# bpod_stepper_1_4_1.net
KiCad netlist of a schematic drawn in EAGLE
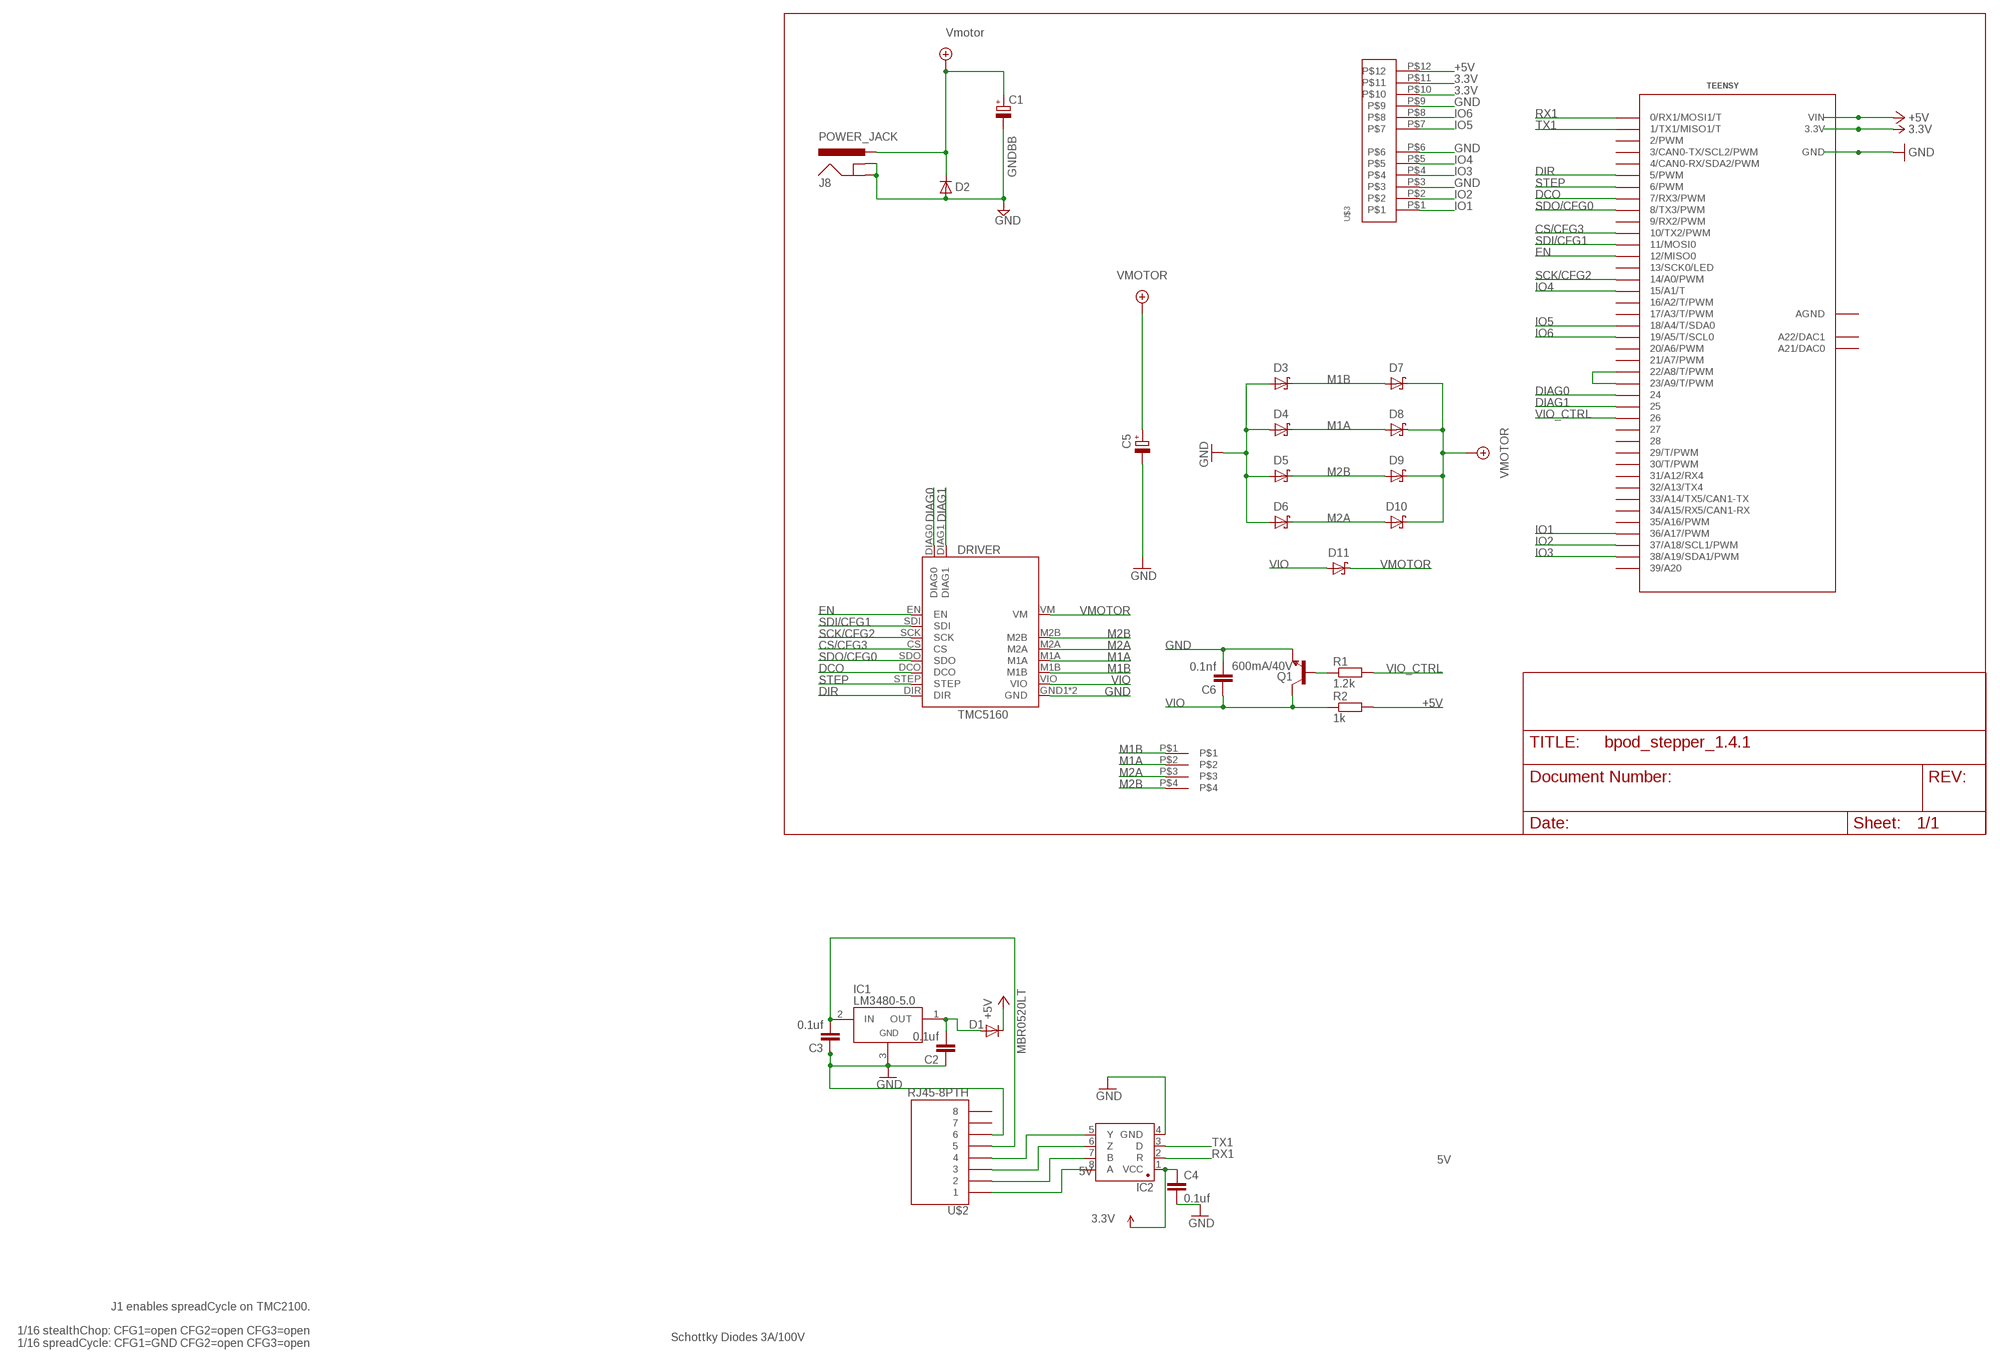
[diagram p0: schematic, sheet 1]

(export (version "E")
  (design (tool "Eeschema 10.0.6"))
  (components
    (comp (ref "C1")
      (value "CPOL-EUG")
      (footprint "eagle-import:PANASONIC_G")
      (libsource (lib "eagle-import") (part "CPOL-EUG"))
    )
    (comp (ref "C2")
      (value "0.1uf")
      (footprint "eagle-import:1206@1")
      (libsource (lib "eagle-import") (part "CAP1206"))
    )
    (comp (ref "C3")
      (value "0.1uf")
      (footprint "eagle-import:1206@1")
      (libsource (lib "eagle-import") (part "CAP1206"))
    )
    (comp (ref "C4")
      (value "0.1uf")
      (footprint "eagle-import:1206@1")
      (libsource (lib "eagle-import") (part "CAP1206"))
    )
    (comp (ref "C5")
      (value "CPOL-EUG")
      (footprint "eagle-import:PANASONIC_G")
      (libsource (lib "eagle-import") (part "CPOL-EUG"))
    )
    (comp (ref "C6")
      (value "0.1nf")
      (footprint "eagle-import:1206@1")
      (libsource (lib "eagle-import") (part "CAP1206"))
    )
    (comp (ref "D1")
      (value "MBR0520LT")
      (footprint "eagle-import:SOD123")
      (libsource (lib "eagle-import") (part "MBR0520LT"))
    )
    (comp (ref "D2")
      (value "DIODE-DO214AA")
      (footprint "eagle-import:DO214AA")
      (libsource (lib "eagle-import") (part "DIODE-DO214AA"))
    )
    (comp (ref "D3")
      (value "S310FA")
      (footprint "eagle-import:SOD123")
      (libsource (lib "eagle-import") (part "D_SCHOTTKY-SOD123"))
    )
    (comp (ref "D4")
      (value "S310FA")
      (footprint "eagle-import:SOD123")
      (libsource (lib "eagle-import") (part "D_SCHOTTKY-SOD123"))
    )
    (comp (ref "D5")
      (value "S310FA")
      (footprint "eagle-import:SOD123")
      (libsource (lib "eagle-import") (part "D_SCHOTTKY-SOD123"))
    )
    (comp (ref "D6")
      (value "S310FA")
      (footprint "eagle-import:SOD123")
      (libsource (lib "eagle-import") (part "D_SCHOTTKY-SOD123"))
    )
    (comp (ref "D7")
      (value "S310FA")
      (footprint "eagle-import:SOD123")
      (libsource (lib "eagle-import") (part "D_SCHOTTKY-SOD123"))
    )
    (comp (ref "D8")
      (value "S310FA")
      (footprint "eagle-import:SOD123")
      (libsource (lib "eagle-import") (part "D_SCHOTTKY-SOD123"))
    )
    (comp (ref "D9")
      (value "S310FA")
      (footprint "eagle-import:SOD123")
      (libsource (lib "eagle-import") (part "D_SCHOTTKY-SOD123"))
    )
    (comp (ref "D10")
      (value "S310FA")
      (footprint "eagle-import:SOD123")
      (libsource (lib "eagle-import") (part "D_SCHOTTKY-SOD123"))
    )
    (comp (ref "D11")
      (value "S310FA")
      (footprint "eagle-import:SOD123")
      (libsource (lib "eagle-import") (part "D_SCHOTTKY-SOD123"))
    )
    (comp (ref "DRIVER")
      (value "TMC5160")
      (footprint "eagle-import:TMC5160")
      (libsource (lib "eagle-import") (part "TMC5160"))
    )
    (comp (ref "IC1")
      (value "LM3480-5.0")
      (footprint "eagle-import:SOT-23-3")
      (libsource (lib "eagle-import") (part "LM3480-5.0"))
    )
    (comp (ref "IC2")
      (value "SN65HVD31DR")
      (footprint "eagle-import:SO08")
      (libsource (lib "eagle-import") (part "SN65HVD31DR"))
    )
    (comp (ref "J8")
      (value "POWER_JACK")
      (footprint "eagle-import:POWER_JACK_PTH")
      (libsource (lib "eagle-import") (part "POWER_JACK"))
    )
    (comp (ref "Q1")
      (value "600mA/40V")
      (footprint "eagle-import:SOT23-3")
      (libsource (lib "eagle-import") (part "TRANS_NPN-MMBT2222AL"))
    )
    (comp (ref "R1")
      (value "1.2k")
      (footprint "eagle-import:R1206")
      (libsource (lib "eagle-import") (part "R-EU_R1206"))
    )
    (comp (ref "R2")
      (value "1k")
      (footprint "eagle-import:R1206")
      (libsource (lib "eagle-import") (part "R-EU_R1206"))
    )
    (comp (ref "TEENSY")
      (value "TEENSY_3.6_DIL")
      (footprint "eagle-import:TEENSY_3.6_DIL")
      (libsource (lib "eagle-import") (part "TEENSY_3.6_DIL"))
    )
    (comp (ref "U$2")
      (value "RJ45-8PTH")
      (footprint "eagle-import:RJ45-8")
      (libsource (lib "eagle-import") (part "RJ45-8PTH"))
    )
    (comp (ref "U$3")
      (value "12POS_MOLEX_SOCKET")
      (footprint "eagle-import:12POS_MOLEX_SOCKET")
      (libsource (lib "eagle-import") (part "12POS_MOLEX_SOCKET"))
    )
    (comp (ref "U$4")
      (value "MOLEX395221004")
      (footprint "eagle-import:MOLEX395221004")
      (libsource (lib "eagle-import") (part "MOLEX395221004"))
    )
  )
  (nets
    (net (code "1") (name "+5V") (class "Default")
      (node (ref "D1") (pin "C") (pinfunction "C_C") (pintype "passive"))
      (node (ref "R2") (pin "2") (pinfunction "2_2") (pintype "passive"))
      (node (ref "TEENSY") (pin "VIN") (pinfunction "VIN_VIN") (pintype "power_in"))
      (node (ref "U$3") (pin "P$12") (pinfunction "P$12_P$12") (pintype "bidirectional"))
    )
    (net (code "2") (name "/AGND") (class "Default")
      (node (ref "TEENSY") (pin "AGND") (pinfunction "AGND_AGND") (pintype "power_in"))
    )
    (net (code "3") (name "/CS{slash}CFG3") (class "Default")
      (node (ref "DRIVER") (pin "CS") (pinfunction "CS_CS") (pintype "passive"))
      (node (ref "TEENSY") (pin "10") (pinfunction "10/TX2/PWM_10") (pintype "bidirectional"))
    )
    (net (code "4") (name "/DCO") (class "Default")
      (node (ref "DRIVER") (pin "DCO") (pinfunction "DCO_DCO") (pintype "passive"))
      (node (ref "TEENSY") (pin "7") (pinfunction "7/RX3/PWM_7") (pintype "bidirectional"))
    )
    (net (code "5") (name "/DIAG0") (class "Default")
      (node (ref "DRIVER") (pin "DIAG0") (pinfunction "DIAG0_DIAG0") (pintype "passive"))
      (node (ref "TEENSY") (pin "24") (pinfunction "24_24") (pintype "bidirectional"))
    )
    (net (code "6") (name "/DIAG1") (class "Default")
      (node (ref "DRIVER") (pin "DIAG1") (pinfunction "DIAG1_DIAG1") (pintype "passive"))
      (node (ref "TEENSY") (pin "25") (pinfunction "25_25") (pintype "bidirectional"))
    )
    (net (code "7") (name "/DIR") (class "Default")
      (node (ref "DRIVER") (pin "DIR") (pinfunction "DIR_DIR") (pintype "input"))
      (node (ref "TEENSY") (pin "5") (pinfunction "5/PWM_5") (pintype "bidirectional"))
    )
    (net (code "8") (name "/EN") (class "Default")
      (node (ref "DRIVER") (pin "EN") (pinfunction "EN_EN") (pintype "passive"))
      (node (ref "TEENSY") (pin "12") (pinfunction "12/MISO0_12") (pintype "bidirectional"))
    )
    (net (code "9") (name "/IO1") (class "Default")
      (node (ref "TEENSY") (pin "36/A17") (pinfunction "36/A17/PWM_36/A17") (pintype "bidirectional"))
      (node (ref "U$3") (pin "P$1") (pinfunction "P$1_P$1") (pintype "bidirectional"))
    )
    (net (code "10") (name "/IO2") (class "Default")
      (node (ref "TEENSY") (pin "37/A18") (pinfunction "37/A18/SCL1/PWM_37/A18") (pintype "bidirectional"))
      (node (ref "U$3") (pin "P$2") (pinfunction "P$2_P$2") (pintype "bidirectional"))
    )
    (net (code "11") (name "/IO3") (class "Default")
      (node (ref "TEENSY") (pin "38/A19") (pinfunction "38/A19/SDA1/PWM_38/A19") (pintype "bidirectional"))
      (node (ref "U$3") (pin "P$4") (pinfunction "P$4_P$4") (pintype "bidirectional"))
    )
    (net (code "12") (name "/IO4") (class "Default")
      (node (ref "TEENSY") (pin "15/A1") (pinfunction "15/A1/T_15/A1") (pintype "bidirectional"))
      (node (ref "U$3") (pin "P$5") (pinfunction "P$5_P$5") (pintype "bidirectional"))
    )
    (net (code "13") (name "/IO5") (class "Default")
      (node (ref "TEENSY") (pin "18/A4") (pinfunction "18/A4/T/SDA0_18/A4") (pintype "bidirectional"))
      (node (ref "U$3") (pin "P$7") (pinfunction "P$7_P$7") (pintype "bidirectional"))
    )
    (net (code "14") (name "/IO6") (class "Default")
      (node (ref "TEENSY") (pin "19/A5") (pinfunction "19/A5/T/SCL0_19/A5") (pintype "bidirectional"))
      (node (ref "U$3") (pin "P$8") (pinfunction "P$8_P$8") (pintype "bidirectional"))
    )
    (net (code "15") (name "/M1A") (class "Default")
      (node (ref "D4") (pin "C") (pinfunction "C_C") (pintype "passive"))
      (node (ref "D8") (pin "A") (pinfunction "A_A") (pintype "passive"))
      (node (ref "DRIVER") (pin "M1A") (pinfunction "M1A_M1A") (pintype "output"))
      (node (ref "U$4") (pin "P$2") (pinfunction "P$2_P$2") (pintype "bidirectional"))
    )
    (net (code "16") (name "/M1B") (class "Default")
      (node (ref "D3") (pin "C") (pinfunction "C_C") (pintype "passive"))
      (node (ref "D7") (pin "A") (pinfunction "A_A") (pintype "passive"))
      (node (ref "DRIVER") (pin "M1B") (pinfunction "M1B_M1B") (pintype "output"))
      (node (ref "U$4") (pin "P$1") (pinfunction "P$1_P$1") (pintype "bidirectional"))
    )
    (net (code "17") (name "/M2A") (class "Default")
      (node (ref "D10") (pin "A") (pinfunction "A_A") (pintype "passive"))
      (node (ref "D6") (pin "C") (pinfunction "C_C") (pintype "passive"))
      (node (ref "DRIVER") (pin "M2A") (pinfunction "M2A_M2A") (pintype "output"))
      (node (ref "U$4") (pin "P$3") (pinfunction "P$3_P$3") (pintype "bidirectional"))
    )
    (net (code "18") (name "/M2B") (class "Default")
      (node (ref "D5") (pin "C") (pinfunction "C_C") (pintype "passive"))
      (node (ref "D9") (pin "A") (pinfunction "A_A") (pintype "passive"))
      (node (ref "DRIVER") (pin "M2B") (pinfunction "M2B_M2B") (pintype "output"))
      (node (ref "U$4") (pin "P$4") (pinfunction "P$4_P$4") (pintype "bidirectional"))
    )
    (net (code "19") (name "/RX1") (class "Default")
      (node (ref "IC2") (pin "2") (pinfunction "R_2") (pintype "bidirectional"))
      (node (ref "TEENSY") (pin "0") (pinfunction "0/RX1/MOSI1/T_0") (pintype "bidirectional"))
    )
    (net (code "20") (name "/SCK{slash}CFG2") (class "Default")
      (node (ref "DRIVER") (pin "SCK") (pinfunction "SCK_SCK") (pintype "passive"))
      (node (ref "TEENSY") (pin "14/A0") (pinfunction "14/A0/PWM_14/A0") (pintype "bidirectional"))
    )
    (net (code "21") (name "/SDI{slash}CFG1") (class "Default")
      (node (ref "DRIVER") (pin "SDI") (pinfunction "SDI_SDI") (pintype "passive"))
      (node (ref "TEENSY") (pin "11") (pinfunction "11/MOSI0_11") (pintype "bidirectional"))
    )
    (net (code "22") (name "/SDO{slash}CFG0") (class "Default")
      (node (ref "DRIVER") (pin "SDO") (pinfunction "SDO_SDO") (pintype "passive"))
      (node (ref "TEENSY") (pin "8") (pinfunction "8/TX3/PWM_8") (pintype "bidirectional"))
    )
    (net (code "23") (name "/STEP") (class "Default")
      (node (ref "DRIVER") (pin "STEP") (pinfunction "STEP_STEP") (pintype "input"))
      (node (ref "TEENSY") (pin "6") (pinfunction "6/PWM_6") (pintype "bidirectional"))
    )
    (net (code "24") (name "/TX1") (class "Default")
      (node (ref "IC2") (pin "3") (pinfunction "D_3") (pintype "bidirectional"))
      (node (ref "TEENSY") (pin "1") (pinfunction "1/TX1/MISO1/T_1") (pintype "bidirectional"))
    )
    (net (code "25") (name "/VIO") (class "Default")
      (node (ref "C6") (pin "1") (pinfunction "1_1") (pintype "passive"))
      (node (ref "D11") (pin "A") (pinfunction "A_A") (pintype "passive"))
      (node (ref "DRIVER") (pin "VIO") (pinfunction "VIO_VIO") (pintype "power_in"))
      (node (ref "Q1") (pin "3") (pinfunction "C_3") (pintype "passive"))
      (node (ref "R2") (pin "1") (pinfunction "1_1") (pintype "passive"))
    )
    (net (code "26") (name "/VIO_CTRL") (class "Default")
      (node (ref "R1") (pin "2") (pinfunction "2_2") (pintype "passive"))
      (node (ref "TEENSY") (pin "26") (pinfunction "26_26") (pintype "bidirectional"))
    )
    (net (code "27") (name "3.3V") (class "Default")
      (node (ref "C4") (pin "1") (pinfunction "1_1") (pintype "passive"))
      (node (ref "IC2") (pin "1") (pinfunction "VCC_1") (pintype "bidirectional"))
      (node (ref "TEENSY") (pin "3.3V") (pinfunction "3.3V_3.3V") (pintype "power_in"))
      (node (ref "TEENSY") (pin "3.3V3") (pinfunction "3.3V_3.3V3") (pintype "power_in"))
      (node (ref "U$3") (pin "P$10") (pinfunction "P$10_P$10") (pintype "bidirectional"))
      (node (ref "U$3") (pin "P$11") (pinfunction "P$11_P$11") (pintype "bidirectional"))
    )
    (net (code "28") (name "GND") (class "Default")
      (node (ref "C1") (pin "-") (pinfunction "-_-") (pintype "passive"))
      (node (ref "C2") (pin "1") (pinfunction "1_1") (pintype "passive"))
      (node (ref "C3") (pin "1") (pinfunction "1_1") (pintype "passive"))
      (node (ref "C4") (pin "2") (pinfunction "2_2") (pintype "passive"))
      (node (ref "C5") (pin "-") (pinfunction "-_-") (pintype "passive"))
      (node (ref "C6") (pin "2") (pinfunction "2_2") (pintype "passive"))
      (node (ref "D2") (pin "A") (pinfunction "A_A") (pintype "passive"))
      (node (ref "D3") (pin "A") (pinfunction "A_A") (pintype "passive"))
      (node (ref "D4") (pin "A") (pinfunction "A_A") (pintype "passive"))
      (node (ref "D5") (pin "A") (pinfunction "A_A") (pintype "passive"))
      (node (ref "D6") (pin "A") (pinfunction "A_A") (pintype "passive"))
      (node (ref "DRIVER") (pin "GND1") (pinfunction "GND_GND1") (pintype "power_in"))
      (node (ref "DRIVER") (pin "GND2") (pinfunction "GND_GND2") (pintype "power_in"))
      (node (ref "IC1") (pin "3") (pinfunction "GND_3") (pintype "power_in"))
      (node (ref "IC2") (pin "4") (pinfunction "GND_4") (pintype "bidirectional"))
      (node (ref "J8") (pin "GND") (pinfunction "GND_GND") (pintype "bidirectional"))
      (node (ref "J8") (pin "GNDBREAK") (pinfunction "GNDBREAK_GNDBREAK") (pintype "bidirectional"))
      (node (ref "Q1") (pin "2") (pinfunction "E_2") (pintype "passive"))
      (node (ref "TEENSY") (pin "GND") (pinfunction "GND_GND") (pintype "power_in"))
      (node (ref "TEENSY") (pin "GND1") (pinfunction "GND_GND1") (pintype "power_in"))
      (node (ref "U$2") (pin "6") (pinfunction "6_6") (pintype "bidirectional"))
      (node (ref "U$3") (pin "P$3") (pinfunction "P$3_P$3") (pintype "bidirectional"))
      (node (ref "U$3") (pin "P$6") (pinfunction "P$6_P$6") (pintype "bidirectional"))
      (node (ref "U$3") (pin "P$9") (pinfunction "P$9_P$9") (pintype "bidirectional"))
    )
    (net (code "29") (name "Net-(IC1-IN)") (class "Default")
      (node (ref "C3") (pin "2") (pinfunction "2_2") (pintype "passive"))
      (node (ref "IC1") (pin "2") (pinfunction "IN_2") (pintype "power_in"))
      (node (ref "U$2") (pin "5") (pinfunction "5_5") (pintype "bidirectional"))
    )
    (net (code "30") (name "Net-(IC1-OUT)") (class "Default")
      (node (ref "C2") (pin "2") (pinfunction "2_2") (pintype "passive"))
      (node (ref "D1") (pin "A") (pinfunction "A_A") (pintype "passive"))
      (node (ref "IC1") (pin "1") (pinfunction "OUT_1") (pintype "power_in"))
    )
    (net (code "31") (name "Net-(IC2-A)") (class "Default")
      (node (ref "IC2") (pin "8") (pinfunction "A_8") (pintype "bidirectional"))
      (node (ref "U$2") (pin "1") (pinfunction "1_1") (pintype "bidirectional"))
    )
    (net (code "32") (name "Net-(IC2-B)") (class "Default")
      (node (ref "IC2") (pin "7") (pinfunction "B_7") (pintype "bidirectional"))
      (node (ref "U$2") (pin "2") (pinfunction "2_2") (pintype "bidirectional"))
    )
    (net (code "33") (name "Net-(IC2-Y)") (class "Default")
      (node (ref "IC2") (pin "5") (pinfunction "Y_5") (pintype "bidirectional"))
      (node (ref "U$2") (pin "4") (pinfunction "4_4") (pintype "bidirectional"))
    )
    (net (code "34") (name "Net-(IC2-Z)") (class "Default")
      (node (ref "IC2") (pin "6") (pinfunction "Z_6") (pintype "bidirectional"))
      (node (ref "U$2") (pin "3") (pinfunction "3_3") (pintype "bidirectional"))
    )
    (net (code "35") (name "Net-(Q1-B)") (class "Default")
      (node (ref "Q1") (pin "1") (pinfunction "B_1") (pintype "passive"))
      (node (ref "R1") (pin "1") (pinfunction "1_1") (pintype "passive"))
    )
    (net (code "36") (name "Net-(TEENSY-22{slash}A8{slash}T{slash}PWM)") (class "Default")
      (node (ref "TEENSY") (pin "22/A8") (pinfunction "22/A8/T/PWM_22/A8") (pintype "bidirectional"))
      (node (ref "TEENSY") (pin "23/A9") (pinfunction "23/A9/T/PWM_23/A9") (pintype "bidirectional"))
    )
    (net (code "37") (name "Vmotor") (class "Default")
      (node (ref "C1") (pin "+") (pinfunction "+_+") (pintype "passive"))
      (node (ref "C5") (pin "+") (pinfunction "+_+") (pintype "passive"))
      (node (ref "D10") (pin "C") (pinfunction "C_C") (pintype "passive"))
      (node (ref "D11") (pin "C") (pinfunction "C_C") (pintype "passive"))
      (node (ref "D2") (pin "C") (pinfunction "C_C") (pintype "passive"))
      (node (ref "D7") (pin "C") (pinfunction "C_C") (pintype "passive"))
      (node (ref "D8") (pin "C") (pinfunction "C_C") (pintype "passive"))
      (node (ref "D9") (pin "C") (pinfunction "C_C") (pintype "passive"))
      (node (ref "DRIVER") (pin "VM") (pinfunction "VM_VM") (pintype "power_in"))
      (node (ref "J8") (pin "PWR") (pinfunction "PWR_PWR") (pintype "bidirectional"))
    )
    (net (code "38") (name "unconnected-(TEENSY-2{slash}PWM-Pad2)") (class "Default")
      (node (ref "TEENSY") (pin "2") (pinfunction "2/PWM_2") (pintype "bidirectional"))
    )
    (net (code "39") (name "unconnected-(TEENSY-3{slash}CAN0-TX{slash}SCL2{slash}PWM-Pad3)") (class "Default")
      (node (ref "TEENSY") (pin "3") (pinfunction "3/CAN0-TX/SCL2/PWM_3") (pintype "bidirectional"))
    )
    (net (code "40") (name "unconnected-(TEENSY-4{slash}CAN0-RX{slash}SDA2{slash}PWM-Pad4)") (class "Default")
      (node (ref "TEENSY") (pin "4") (pinfunction "4/CAN0-RX/SDA2/PWM_4") (pintype "bidirectional"))
    )
    (net (code "41") (name "unconnected-(TEENSY-9{slash}RX2{slash}PWM-Pad9)") (class "Default")
      (node (ref "TEENSY") (pin "9") (pinfunction "9/RX2/PWM_9") (pintype "bidirectional"))
    )
    (net (code "42") (name "unconnected-(TEENSY-13{slash}SCK0{slash}LED-Pad13)") (class "Default")
      (node (ref "TEENSY") (pin "13") (pinfunction "13/SCK0/LED_13") (pintype "bidirectional"))
    )
    (net (code "43") (name "unconnected-(TEENSY-16{slash}A2{slash}T{slash}PWM-Pad16{slash}A2)") (class "Default")
      (node (ref "TEENSY") (pin "16/A2") (pinfunction "16/A2/T/PWM_16/A2") (pintype "bidirectional"))
    )
    (net (code "44") (name "unconnected-(TEENSY-17{slash}A3{slash}T{slash}PWM-Pad17{slash}A3)") (class "Default")
      (node (ref "TEENSY") (pin "17/A3") (pinfunction "17/A3/T/PWM_17/A3") (pintype "bidirectional"))
    )
    (net (code "45") (name "unconnected-(TEENSY-20{slash}A6{slash}PWM-Pad20{slash}A6)") (class "Default")
      (node (ref "TEENSY") (pin "20/A6") (pinfunction "20/A6/PWM_20/A6") (pintype "bidirectional"))
    )
    (net (code "46") (name "unconnected-(TEENSY-21{slash}A7{slash}PWM-Pad21{slash}A7)") (class "Default")
      (node (ref "TEENSY") (pin "21/A7") (pinfunction "21/A7/PWM_21/A7") (pintype "bidirectional"))
    )
    (net (code "47") (name "unconnected-(TEENSY-29{slash}T{slash}PWM-Pad29)") (class "Default")
      (node (ref "TEENSY") (pin "29") (pinfunction "29/T/PWM_29") (pintype "bidirectional"))
    )
    (net (code "48") (name "unconnected-(TEENSY-30{slash}T{slash}PWM-Pad30)") (class "Default")
      (node (ref "TEENSY") (pin "30") (pinfunction "30/T/PWM_30") (pintype "bidirectional"))
    )
    (net (code "49") (name "unconnected-(TEENSY-31{slash}A12{slash}RX4-Pad31{slash}A12)") (class "Default")
      (node (ref "TEENSY") (pin "31/A12") (pinfunction "31/A12/RX4_31/A12") (pintype "bidirectional"))
    )
    (net (code "50") (name "unconnected-(TEENSY-32{slash}A13{slash}TX4-Pad32{slash}A13)") (class "Default")
      (node (ref "TEENSY") (pin "32/A13") (pinfunction "32/A13/TX4_32/A13") (pintype "bidirectional"))
    )
    (net (code "51") (name "unconnected-(TEENSY-33{slash}A14{slash}TX5{slash}CAN1-TX-Pad33{slash}A14)") (class "Default")
      (node (ref "TEENSY") (pin "33/A14") (pinfunction "33/A14/TX5/CAN1-TX_33/A14") (pintype "bidirectional"))
    )
    (net (code "52") (name "unconnected-(TEENSY-34{slash}A15{slash}RX5{slash}CAN1-RX-Pad34{slash}A15)") (class "Default")
      (node (ref "TEENSY") (pin "34/A15") (pinfunction "34/A15/RX5/CAN1-RX_34/A15") (pintype "bidirectional"))
    )
    (net (code "53") (name "unconnected-(TEENSY-35{slash}A16{slash}PWM-Pad35{slash}A16)") (class "Default")
      (node (ref "TEENSY") (pin "35/A16") (pinfunction "35/A16/PWM_35/A16") (pintype "bidirectional"))
    )
    (net (code "54") (name "unconnected-(TEENSY-A21{slash}DAC0-PadA21)") (class "Default")
      (node (ref "TEENSY") (pin "A21") (pinfunction "A21/DAC0_A21") (pintype "bidirectional"))
    )
    (net (code "55") (name "unconnected-(TEENSY-A22{slash}DAC1-PadA22)") (class "Default")
      (node (ref "TEENSY") (pin "A22") (pinfunction "A22/DAC1_A22") (pintype "bidirectional"))
    )
    (net (code "56") (name "unconnected-(TEENSY-Pad27)") (class "Default")
      (node (ref "TEENSY") (pin "27") (pinfunction "27_27") (pintype "bidirectional"))
    )
    (net (code "57") (name "unconnected-(TEENSY-Pad28)") (class "Default")
      (node (ref "TEENSY") (pin "28") (pinfunction "28_28") (pintype "bidirectional"))
    )
    (net (code "58") (name "unconnected-(TEENSY-Pad39{slash}A20)") (class "Default")
      (node (ref "TEENSY") (pin "39/A20") (pinfunction "39/A20_39/A20") (pintype "bidirectional"))
    )
    (net (code "59") (name "unconnected-(U$2-Pad7)") (class "Default")
      (node (ref "U$2") (pin "7") (pinfunction "7_7") (pintype "bidirectional"))
    )
    (net (code "60") (name "unconnected-(U$2-Pad8)") (class "Default")
      (node (ref "U$2") (pin "8") (pinfunction "8_8") (pintype "bidirectional"))
    )
  )
)
